# ygl_energy_monitor.net
KiCad netlist of a schematic drawn in EAGLE
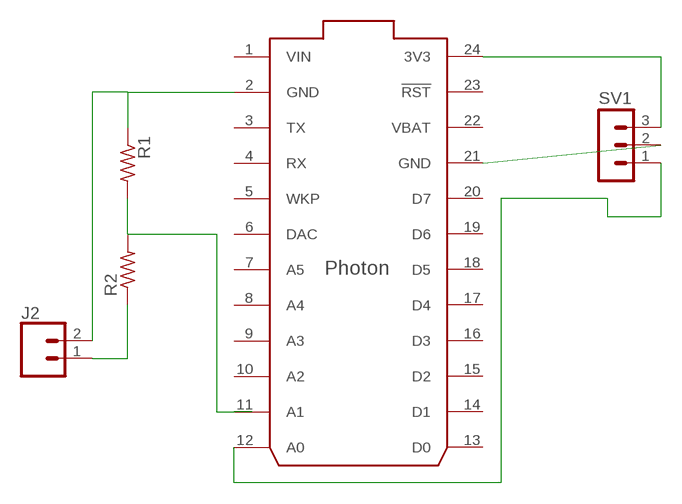
[diagram p0: schematic, sheet 1]

(export (version "E")
  (design (tool "Eeschema 10.0.6"))
  (components
    (comp (ref "J2")
      (value "CONN_023.5MM")
      (footprint "eagle-import:SCREWTERMINAL-3.5MM-2")
      (libsource (lib "eagle-import") (part "CONN_023.5MM"))
    )
    (comp (ref "R1")
      (value "R-US_0207/10")
      (footprint "eagle-import:0207_10")
      (libsource (lib "eagle-import") (part "R-US_0207/10"))
    )
    (comp (ref "R2")
      (value "R-US_0207/10")
      (footprint "eagle-import:0207_10")
      (libsource (lib "eagle-import") (part "R-US_0207/10"))
    )
    (comp (ref "SV1")
      (value "MA03-1")
      (footprint "eagle-import:MA03-1")
      (libsource (lib "eagle-import") (part "MA03-1"))
    )
    (comp (ref "U$1")
      (value "PHOTON_WITH_HEADERS")
      (footprint "eagle-import:PHOTON")
      (libsource (lib "eagle-import") (part "PHOTON_WITH_HEADERS"))
    )
  )
  (nets
    (net (code "1") (name "/VBAT") (class "Default")
      (node (ref "U$1") (pin "22") (pinfunction "VBAT_22") (pintype "power_in"))
    )
    (net (code "2") (name "/VIN") (class "Default")
      (node (ref "U$1") (pin "1") (pinfunction "VIN_1") (pintype "power_in"))
    )
    (net (code "3") (name "Net-(J2-Pad1)") (class "Default")
      (node (ref "J2") (pin "1") (pinfunction "1_1") (pintype "passive"))
      (node (ref "R2") (pin "1") (pinfunction "1_1") (pintype "passive"))
    )
    (net (code "4") (name "Net-(J2-Pad2)") (class "Default")
      (node (ref "J2") (pin "2") (pinfunction "2_2") (pintype "passive"))
      (node (ref "R1") (pin "1") (pinfunction "1_1") (pintype "passive"))
      (node (ref "U$1") (pin "2") (pinfunction "GND_2") (pintype "power_in"))
    )
    (net (code "5") (name "Net-(SV1-Pad2)") (class "Default")
      (node (ref "SV1") (pin "2") (pinfunction "2_2") (pintype "passive"))
      (node (ref "U$1") (pin "21") (pinfunction "GND_21") (pintype "power_in"))
    )
    (net (code "6") (name "Net-(U$1-3V3)") (class "Default")
      (node (ref "SV1") (pin "3") (pinfunction "3_3") (pintype "passive"))
      (node (ref "U$1") (pin "24") (pinfunction "3V3_24") (pintype "power_in"))
    )
    (net (code "7") (name "Net-(U$1-A0)") (class "Default")
      (node (ref "SV1") (pin "1") (pinfunction "1_1") (pintype "passive"))
      (node (ref "U$1") (pin "12") (pinfunction "A0_12") (pintype "bidirectional"))
    )
    (net (code "8") (name "Net-(U$1-A1)") (class "Default")
      (node (ref "R1") (pin "2") (pinfunction "2_2") (pintype "passive"))
      (node (ref "R2") (pin "2") (pinfunction "2_2") (pintype "passive"))
      (node (ref "U$1") (pin "11") (pinfunction "A1_11") (pintype "bidirectional"))
    )
    (net (code "9") (name "unconnected-(U$1-A2-Pad10)") (class "Default")
      (node (ref "U$1") (pin "10") (pinfunction "A2_10") (pintype "bidirectional"))
    )
    (net (code "10") (name "unconnected-(U$1-A3-Pad9)") (class "Default")
      (node (ref "U$1") (pin "9") (pinfunction "A3_9") (pintype "bidirectional"))
    )
    (net (code "11") (name "unconnected-(U$1-A4-Pad8)") (class "Default")
      (node (ref "U$1") (pin "8") (pinfunction "A4_8") (pintype "bidirectional"))
    )
    (net (code "12") (name "unconnected-(U$1-A5-Pad7)") (class "Default")
      (node (ref "U$1") (pin "7") (pinfunction "A5_7") (pintype "bidirectional"))
    )
    (net (code "13") (name "unconnected-(U$1-D0-Pad13)") (class "Default")
      (node (ref "U$1") (pin "13") (pinfunction "D0_13") (pintype "bidirectional"))
    )
    (net (code "14") (name "unconnected-(U$1-D1-Pad14)") (class "Default")
      (node (ref "U$1") (pin "14") (pinfunction "D1_14") (pintype "bidirectional"))
    )
    (net (code "15") (name "unconnected-(U$1-D2-Pad15)") (class "Default")
      (node (ref "U$1") (pin "15") (pinfunction "D2_15") (pintype "bidirectional"))
    )
    (net (code "16") (name "unconnected-(U$1-D3-Pad16)") (class "Default")
      (node (ref "U$1") (pin "16") (pinfunction "D3_16") (pintype "bidirectional"))
    )
    (net (code "17") (name "unconnected-(U$1-D4-Pad17)") (class "Default")
      (node (ref "U$1") (pin "17") (pinfunction "D4_17") (pintype "bidirectional"))
    )
    (net (code "18") (name "unconnected-(U$1-D5-Pad18)") (class "Default")
      (node (ref "U$1") (pin "18") (pinfunction "D5_18") (pintype "bidirectional"))
    )
    (net (code "19") (name "unconnected-(U$1-D6-Pad19)") (class "Default")
      (node (ref "U$1") (pin "19") (pinfunction "D6_19") (pintype "bidirectional"))
    )
    (net (code "20") (name "unconnected-(U$1-D7-Pad20)") (class "Default")
      (node (ref "U$1") (pin "20") (pinfunction "D7_20") (pintype "bidirectional"))
    )
    (net (code "21") (name "unconnected-(U$1-DAC-Pad6)") (class "Default")
      (node (ref "U$1") (pin "6") (pinfunction "DAC_6") (pintype "bidirectional"))
    )
    (net (code "22") (name "unconnected-(U$1-RX-Pad4)") (class "Default")
      (node (ref "U$1") (pin "4") (pinfunction "RX_4") (pintype "bidirectional"))
    )
    (net (code "23") (name "unconnected-(U$1-TX-Pad3)") (class "Default")
      (node (ref "U$1") (pin "3") (pinfunction "TX_3") (pintype "bidirectional"))
    )
    (net (code "24") (name "unconnected-(U$1-WKP-Pad5)") (class "Default")
      (node (ref "U$1") (pin "5") (pinfunction "WKP_5") (pintype "bidirectional"))
    )
    (net (code "25") (name "unconnected-(U$1-~{RST}-Pad23)") (class "Default")
      (node (ref "U$1") (pin "23") (pinfunction "~{RST}_23") (pintype "bidirectional"))
    )
  )
)
